# Sum.net
KiCad netlist of a schematic drawn in Altium Designer
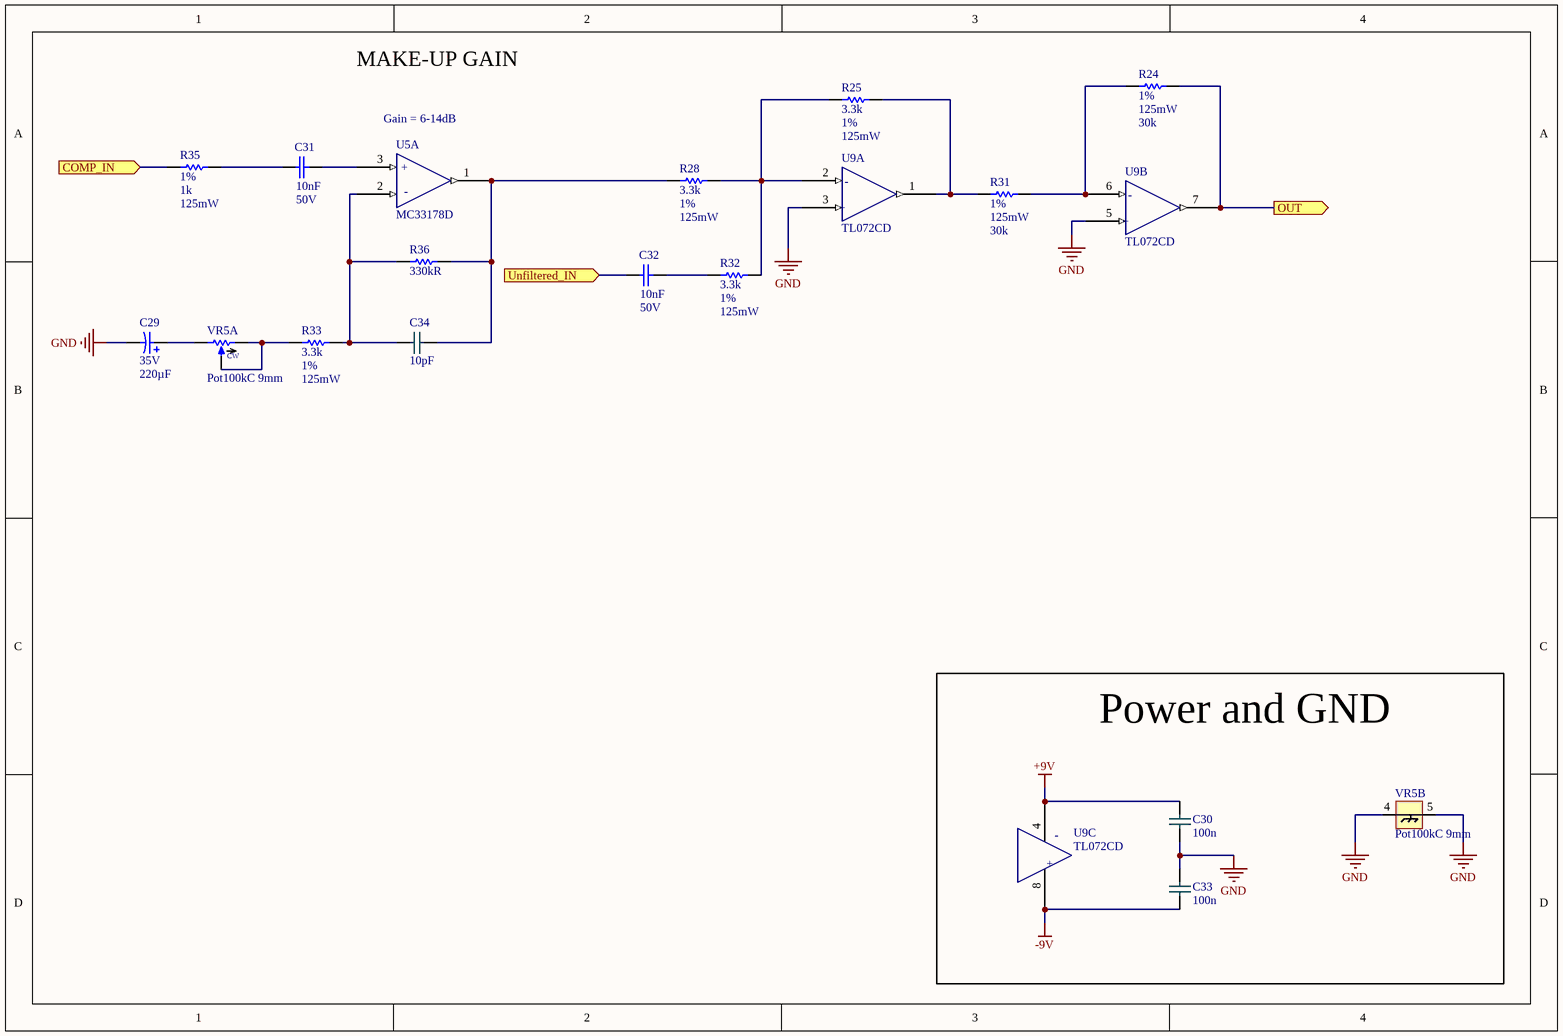
[diagram p0: Sum.SchDoc]

(export (version "E")
  (design (tool "Eeschema 10.0.6"))
  (components
    (comp (ref "C29")
      (value "Cap pol 220µF 35V")
      (footprint "E-CAP, SMT, diameter 10mm, height 10.2mm")
      (description "Cap Aluminum 220uF 35V ±20% (10x10.2mm) SMD 2000h 85°C")
      (fields (field (name "RATED VOLTAGE") "35V") (field (name "CAPACITANCE") "220µF"))
      (libsource (lib "Darkglass Electronics") (part "Capacitor Polarized"))
    )
    (comp (ref "C30")
      (value "100n")
      (footprint "0805-CAP")
      (description "0.1uF 25volts C0G 5%")
      (fields
        (field (name "MOUSER PART") "81-GRM31C5C1E104JA01")
        (field (name "Comment") "Cap 0805 100nF 4")
        (field (name "PUBLISHER") "Altium Limited")
      )
      (libsource (lib "Darkglass Electronics") (part "Capacitor NP"))
    )
    (comp (ref "C31")
      (value "Cap 10nF 0805 C0G")
      (footprint "0805-CAP")
      (description "Cap 10nF 0805 C0G 50V +-5%")
      (fields (field (name "CAPACITANCE") "10nF") (field (name "RATED VOLTAGE") "50V"))
      (libsource (lib "Darkglass Electronics") (part "Capacitor Non-polarized"))
    )
    (comp (ref "C32")
      (value "Cap 10nF 0805 C0G")
      (footprint "0805-CAP")
      (description "Cap 10nF 0805 C0G 50V +-5%")
      (fields (field (name "CAPACITANCE") "10nF") (field (name "RATED VOLTAGE") "50V"))
      (libsource (lib "Darkglass Electronics") (part "Capacitor Non-polarized"))
    )
    (comp (ref "C33")
      (value "100n")
      (footprint "0805-CAP")
      (description "0.1uF 25volts C0G 5%")
      (fields
        (field (name "MOUSER PART") "81-GRM31C5C1E104JA01")
        (field (name "Comment") "Cap 0805 100nF 4")
        (field (name "PUBLISHER") "Altium Limited")
      )
      (libsource (lib "Darkglass Electronics") (part "Capacitor NP"))
    )
    (comp (ref "C34")
      (value "cap 0805 10pF")
      (footprint "0805-CAP")
      (fields (field (name "CAPACITANCE") "10pF"))
      (libsource (lib "Darkglass Electronics") (part "Capacitor NP"))
    )
    (comp (ref "R24")
      (value "Res 30k 1% 0805")
      (footprint "0805-RES")
      (description "Resistor 30k +-1% 0805 Thin film 0.125W +-50ppm/°C")
      (fields
        (field (name "TOLERANCE (+-)") "1%")
        (field (name "POWER") "125mW")
        (field (name "RESISTANCE") "30k")
      )
      (libsource (lib "Darkglass Electronics") (part "Resistor"))
    )
    (comp (ref "R25")
      (value "Res 3.3k 1% 0805")
      (footprint "0805-RES")
      (description "Resistor 3.3k +-1% 0805 Thin film 0.125W +-50ppm/°C")
      (fields
        (field (name "RESISTANCE") "3.3k")
        (field (name "TOLERANCE (+-)") "1%")
        (field (name "POWER") "125mW")
      )
      (libsource (lib "Darkglass Electronics") (part "Resistor"))
    )
    (comp (ref "R28")
      (value "Res 3.3k 1% 0805")
      (footprint "0805-RES")
      (description "Resistor 3.3k +-1% 0805 Thin film 0.125W +-50ppm/°C")
      (fields
        (field (name "RESISTANCE") "3.3k")
        (field (name "TOLERANCE (+-)") "1%")
        (field (name "POWER") "125mW")
      )
      (libsource (lib "Darkglass Electronics") (part "Resistor"))
    )
    (comp (ref "R31")
      (value "Res 30k 1% 0805")
      (footprint "0805-RES")
      (description "Resistor 30k +-1% 0805 Thin film 0.125W +-50ppm/°C")
      (fields
        (field (name "TOLERANCE (+-)") "1%")
        (field (name "POWER") "125mW")
        (field (name "RESISTANCE") "30k")
      )
      (libsource (lib "Darkglass Electronics") (part "Resistor"))
    )
    (comp (ref "R32")
      (value "Res 3.3k 1% 0805")
      (footprint "0805-RES")
      (description "Resistor 3.3k +-1% 0805 Thin film 0.125W +-50ppm/°C")
      (fields
        (field (name "RESISTANCE") "3.3k")
        (field (name "TOLERANCE (+-)") "1%")
        (field (name "POWER") "125mW")
      )
      (libsource (lib "Darkglass Electronics") (part "Resistor"))
    )
    (comp (ref "R33")
      (value "Res 3.3k 1% 0805")
      (footprint "0805-RES")
      (description "Resistor 3.3k +-1% 0805 Thin film 0.125W +-50ppm/°C")
      (fields
        (field (name "RESISTANCE") "3.3k")
        (field (name "TOLERANCE (+-)") "1%")
        (field (name "POWER") "125mW")
      )
      (libsource (lib "Darkglass Electronics") (part "Resistor"))
    )
    (comp (ref "R35")
      (value "Res 1k 1% 0805")
      (footprint "0805-RES")
      (description "Resistor 1k +-1% 0805 Thin film 0.125W +-50ppm/°C")
      (fields
        (field (name "TOLERANCE (+-)") "1%")
        (field (name "RESISTANCE") "1k")
        (field (name "POWER") "125mW")
      )
      (libsource (lib "Darkglass Electronics") (part "Resistor"))
    )
    (comp (ref "R36")
      (value "Res 0805 330k 1%")
      (footprint "0805-RES")
      (description "330kohm, 125mW, 1%, thin film")
      (fields
        (field (name "RESISTANCE") "330kR")
        (field (name "TOLERANCE") "1%")
        (field (name "PUBLISHER") "Altium Limited")
      )
      (libsource (lib "Darkglass Electronics") (part "RES"))
    )
    (comp (ref "U5")
      (value "MC33178D")
      (footprint "SOIC8-127P600X175-8N")
      (description "IC OPAMP GP 5MHZ 8SOIC")
      (fields (field (name "MANUFACTURER") "ON Semiconductor") (field (name "MOUSER PART") "863-MC33178DG"))
      (libsource (lib "Darkglass Electronics") (part "Symbol"))
    )
    (comp (ref "U9")
      (value "TL072CD")
      (footprint "SOIC8-127P600X175-8N")
      (description "Operational Amplifiers - Op Amps Dual Low Noise JFET SOIC8")
      (libsource (lib "Darkglass Electronics") (part "TL072CD"))
    )
    (comp (ref "VR5")
      (value "Pot100kC 9mm")
      (footprint "LJV 9mm pot")
      (description "LJV 9mm pot")
      (fields (field (name "DARKGLASS PART") "D00-0002"))
      (libsource (lib "") (part "Pot100kC 9mm_1"))
    )
  )
  (nets
    (net (code "1") (name "+9V") (class "Default")
      (node (ref "C30") (pin "2") (pinfunction "2_2") (pintype "passive"))
      (node (ref "U9") (pin "4") (pinfunction "V-_4") (pintype "power_in"))
    )
    (net (code "2") (name "-9V") (class "Default")
      (node (ref "C33") (pin "1") (pinfunction "1_1") (pintype "passive"))
      (node (ref "U9") (pin "8") (pinfunction "V+_8") (pintype "power_in"))
    )
    (net (code "3") (name "/COMP_IN") (class "Default")
      (node (ref "R35") (pin "1") (pinfunction "1_1") (pintype "passive"))
    )
    (net (code "4") (name "/OUT") (class "Default")
      (node (ref "R24") (pin "2") (pinfunction "2_2") (pintype "passive"))
      (node (ref "U9") (pin "7") (pinfunction "7_7") (pintype "output"))
    )
    (net (code "5") (name "/Unfiltered_IN") (class "Default")
      (node (ref "C32") (pin "1") (pinfunction "1_1") (pintype "passive"))
    )
    (net (code "6") (name "GND") (class "Default")
      (node (ref "C29") (pin "2") (pinfunction "2_2") (pintype "passive"))
      (node (ref "C30") (pin "1") (pinfunction "1_1") (pintype "passive"))
      (node (ref "C33") (pin "2") (pinfunction "2_2") (pintype "passive"))
      (node (ref "U9") (pin "3") (pinfunction "IN+_3") (pintype "input"))
      (node (ref "U9") (pin "5") (pinfunction "IN+_5") (pintype "input"))
      (node (ref "VR5") (pin "4") (pinfunction "4_4") (pintype "passive"))
      (node (ref "VR5") (pin "5") (pinfunction "5_5") (pintype "passive"))
    )
    (net (code "7") (name "Net-(C31-Pad1)") (class "Default")
      (node (ref "C31") (pin "1") (pinfunction "1_1") (pintype "passive"))
      (node (ref "R35") (pin "2") (pinfunction "2_2") (pintype "passive"))
    )
    (net (code "8") (name "Net-(C31-Pad2)") (class "Default")
      (node (ref "C31") (pin "2") (pinfunction "2_2") (pintype "passive"))
      (node (ref "U5") (pin "3") (pinfunction "3_3") (pintype "input"))
    )
    (net (code "9") (name "Net-(C32-Pad2)") (class "Default")
      (node (ref "C32") (pin "2") (pinfunction "2_2") (pintype "passive"))
      (node (ref "R32") (pin "1") (pinfunction "1_1") (pintype "passive"))
    )
    (net (code "10") (name "Net-(C34-Pad1)") (class "Default")
      (node (ref "C34") (pin "1") (pinfunction "1_1") (pintype "passive"))
      (node (ref "R33") (pin "2") (pinfunction "2_2") (pintype "passive"))
      (node (ref "R36") (pin "1") (pinfunction "1_1") (pintype "passive"))
      (node (ref "U5") (pin "2") (pinfunction "2_2") (pintype "input"))
    )
    (net (code "11") (name "Net-(C34-Pad2)") (class "Default")
      (node (ref "C34") (pin "2") (pinfunction "2_2") (pintype "passive"))
      (node (ref "R28") (pin "1") (pinfunction "1_1") (pintype "passive"))
      (node (ref "R36") (pin "2") (pinfunction "2_2") (pintype "passive"))
      (node (ref "U5") (pin "1") (pinfunction "1_1") (pintype "output"))
    )
    (net (code "12") (name "Net-(U9A-IN-)") (class "Default")
      (node (ref "R25") (pin "1") (pinfunction "1_1") (pintype "passive"))
      (node (ref "R28") (pin "2") (pinfunction "2_2") (pintype "passive"))
      (node (ref "R32") (pin "2") (pinfunction "2_2") (pintype "passive"))
      (node (ref "U9") (pin "2") (pinfunction "IN-_2") (pintype "input"))
    )
    (net (code "13") (name "Net-(U9A-OUT)") (class "Default")
      (node (ref "R25") (pin "2") (pinfunction "2_2") (pintype "passive"))
      (node (ref "R31") (pin "2") (pinfunction "2_2") (pintype "passive"))
      (node (ref "U9") (pin "1") (pinfunction "OUT_1") (pintype "output"))
    )
    (net (code "14") (name "Net-(U9B-IN-)") (class "Default")
      (node (ref "R24") (pin "1") (pinfunction "1_1") (pintype "passive"))
      (node (ref "R31") (pin "1") (pinfunction "1_1") (pintype "passive"))
      (node (ref "U9") (pin "6") (pinfunction "IN-_6") (pintype "input"))
    )
    (net (code "15") (name "Net-(VR5A-CCWPIN)") (class "Default")
      (node (ref "C29") (pin "1") (pinfunction "1_1") (pintype "passive"))
      (node (ref "VR5") (pin "1") (pinfunction "CCWPIN_1") (pintype "passive"))
    )
    (net (code "16") (name "Net-(VR5A-CWPIN)") (class "Default")
      (node (ref "R33") (pin "1") (pinfunction "1_1") (pintype "passive"))
      (node (ref "VR5") (pin "2") (pinfunction "WIPER_2") (pintype "passive"))
      (node (ref "VR5") (pin "3") (pinfunction "CWPIN_3") (pintype "passive"))
    )
  )
)
